# H-Bridge_drive_Sch.net
KiCad netlist of a schematic drawn in Altium Designer
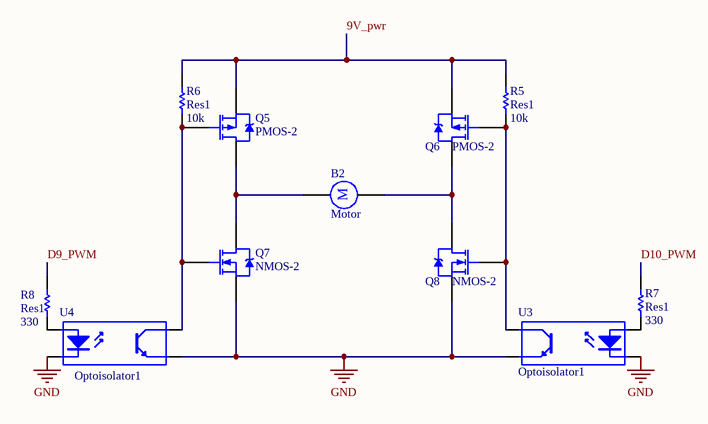
[diagram p0: H-Bridge drive Sch.SchDoc]

(export (version "E")
  (design (tool "Eeschema 10.0.6"))
  (components
    (comp (ref "B2")
      (value "Motor")
      (footprint "HDR1X2")
      (description "Motor, General Kind")
      (fields (field (name "PUBLISHER") "Altium Limited"))
      (libsource (lib "Miscellaneous Devices") (part "Motor"))
    )
    (comp (ref "Q5")
      (value "PMOS-2")
      (footprint "TO-220AB")
      (description "P-Channel Power MOSFET")
      (fields (field (name "PUBLISHER") "Altium Limited"))
      (libsource (lib "Miscellaneous Devices") (part "PMOS-2"))
    )
    (comp (ref "Q6")
      (value "PMOS-2")
      (footprint "TO-220AB")
      (description "P-Channel Power MOSFET")
      (fields (field (name "PUBLISHER") "Altium Limited"))
      (libsource (lib "Miscellaneous Devices") (part "PMOS-2"))
    )
    (comp (ref "Q7")
      (value "NMOS-2")
      (footprint "TO-220AB")
      (description "N-Channel Power MOSFET")
      (fields (field (name "PUBLISHER") "Altium Limited"))
      (libsource (lib "Miscellaneous Devices") (part "NMOS-2"))
    )
    (comp (ref "Q8")
      (value "NMOS-2")
      (footprint "TO-220AB")
      (description "N-Channel Power MOSFET")
      (fields (field (name "PUBLISHER") "Altium Limited"))
      (libsource (lib "Miscellaneous Devices") (part "NMOS-2"))
    )
    (comp (ref "R5")
      (value "Res1")
      (footprint "6-0805_N")
      (description "Resistor")
      (fields (field (name "ALTIUM_VALUE") "10k") (field (name "PUBLISHER") "Altium Limited"))
      (libsource (lib "Miscellaneous Devices") (part "Res1"))
    )
    (comp (ref "R6")
      (value "Res1")
      (footprint "6-0805_N")
      (description "Resistor")
      (fields (field (name "ALTIUM_VALUE") "10k") (field (name "PUBLISHER") "Altium Limited"))
      (libsource (lib "Miscellaneous Devices") (part "Res1"))
    )
    (comp (ref "R7")
      (value "Res1")
      (footprint "6-0805_N")
      (description "Resistor")
      (fields (field (name "ALTIUM_VALUE") "330") (field (name "PUBLISHER") "Altium Limited"))
      (libsource (lib "Miscellaneous Devices") (part "Res1"))
    )
    (comp (ref "R8")
      (value "Res1")
      (footprint "6-0805_N")
      (description "Resistor")
      (fields (field (name "ALTIUM_VALUE") "330") (field (name "PUBLISHER") "Altium Limited"))
      (libsource (lib "Miscellaneous Devices") (part "Res1"))
    )
    (comp (ref "U3")
      (value "Optoisolator1")
      (footprint "DIP-4")
      (description "4-Pin Phototransistor Optocoupler")
      (fields (field (name "PUBLISHER") "Altium Limited"))
      (libsource (lib "Miscellaneous Devices") (part "Optoisolator1"))
    )
    (comp (ref "U4")
      (value "Optoisolator1")
      (footprint "DIP-4")
      (description "4-Pin Phototransistor Optocoupler")
      (fields (field (name "PUBLISHER") "Altium Limited"))
      (libsource (lib "Miscellaneous Devices") (part "Optoisolator1"))
    )
  )
  (nets
    (net (code "1") (name "/9V_pwr") (class "Default")
      (node (ref "Q5") (pin "3") (pinfunction "S_3") (pintype "passive"))
      (node (ref "Q6") (pin "3") (pinfunction "S_3") (pintype "passive"))
      (node (ref "R5") (pin "2") (pinfunction "2_2") (pintype "passive"))
      (node (ref "R6") (pin "2") (pinfunction "2_2") (pintype "passive"))
    )
    (net (code "2") (name "/D9_PWM") (class "Default")
      (node (ref "R8") (pin "2") (pinfunction "2_2") (pintype "passive"))
    )
    (net (code "3") (name "/D10_PWM") (class "Default")
      (node (ref "R7") (pin "2") (pinfunction "2_2") (pintype "passive"))
    )
    (net (code "4") (name "GND") (class "Default")
      (node (ref "Q7") (pin "3") (pinfunction "S_3") (pintype "passive"))
      (node (ref "Q8") (pin "3") (pinfunction "S_3") (pintype "passive"))
      (node (ref "U3") (pin "2") (pinfunction "K_2") (pintype "passive"))
      (node (ref "U3") (pin "3") (pinfunction "E_3") (pintype "passive"))
      (node (ref "U4") (pin "2") (pinfunction "K_2") (pintype "passive"))
      (node (ref "U4") (pin "3") (pinfunction "E_3") (pintype "passive"))
    )
    (net (code "5") (name "Net-(Q5-D)") (class "Default")
      (node (ref "B2") (pin "1") (pinfunction "1_1") (pintype "passive"))
      (node (ref "Q5") (pin "2") (pinfunction "D_2") (pintype "passive"))
      (node (ref "Q7") (pin "2") (pinfunction "D_2") (pintype "passive"))
    )
    (net (code "6") (name "Net-(Q5-G)") (class "Default")
      (node (ref "Q5") (pin "1") (pinfunction "G_1") (pintype "passive"))
      (node (ref "Q7") (pin "1") (pinfunction "G_1") (pintype "passive"))
      (node (ref "R6") (pin "1") (pinfunction "1_1") (pintype "passive"))
      (node (ref "U4") (pin "4") (pinfunction "C_4") (pintype "passive"))
    )
    (net (code "7") (name "Net-(Q6-D)") (class "Default")
      (node (ref "B2") (pin "2") (pinfunction "2_2") (pintype "passive"))
      (node (ref "Q6") (pin "2") (pinfunction "D_2") (pintype "passive"))
      (node (ref "Q8") (pin "2") (pinfunction "D_2") (pintype "passive"))
    )
    (net (code "8") (name "Net-(Q6-G)") (class "Default")
      (node (ref "Q6") (pin "1") (pinfunction "G_1") (pintype "passive"))
      (node (ref "Q8") (pin "1") (pinfunction "G_1") (pintype "passive"))
      (node (ref "R5") (pin "1") (pinfunction "1_1") (pintype "passive"))
      (node (ref "U3") (pin "4") (pinfunction "C_4") (pintype "passive"))
    )
    (net (code "9") (name "Net-(U3-A)") (class "Default")
      (node (ref "R7") (pin "1") (pinfunction "1_1") (pintype "passive"))
      (node (ref "U3") (pin "1") (pinfunction "A_1") (pintype "passive"))
    )
    (net (code "10") (name "Net-(U4-A)") (class "Default")
      (node (ref "R8") (pin "1") (pinfunction "1_1") (pintype "passive"))
      (node (ref "U4") (pin "1") (pinfunction "A_1") (pintype "passive"))
    )
  )
)
